# Control_Interface_Board.net
KiCad netlist of a schematic drawn in Altium Designer
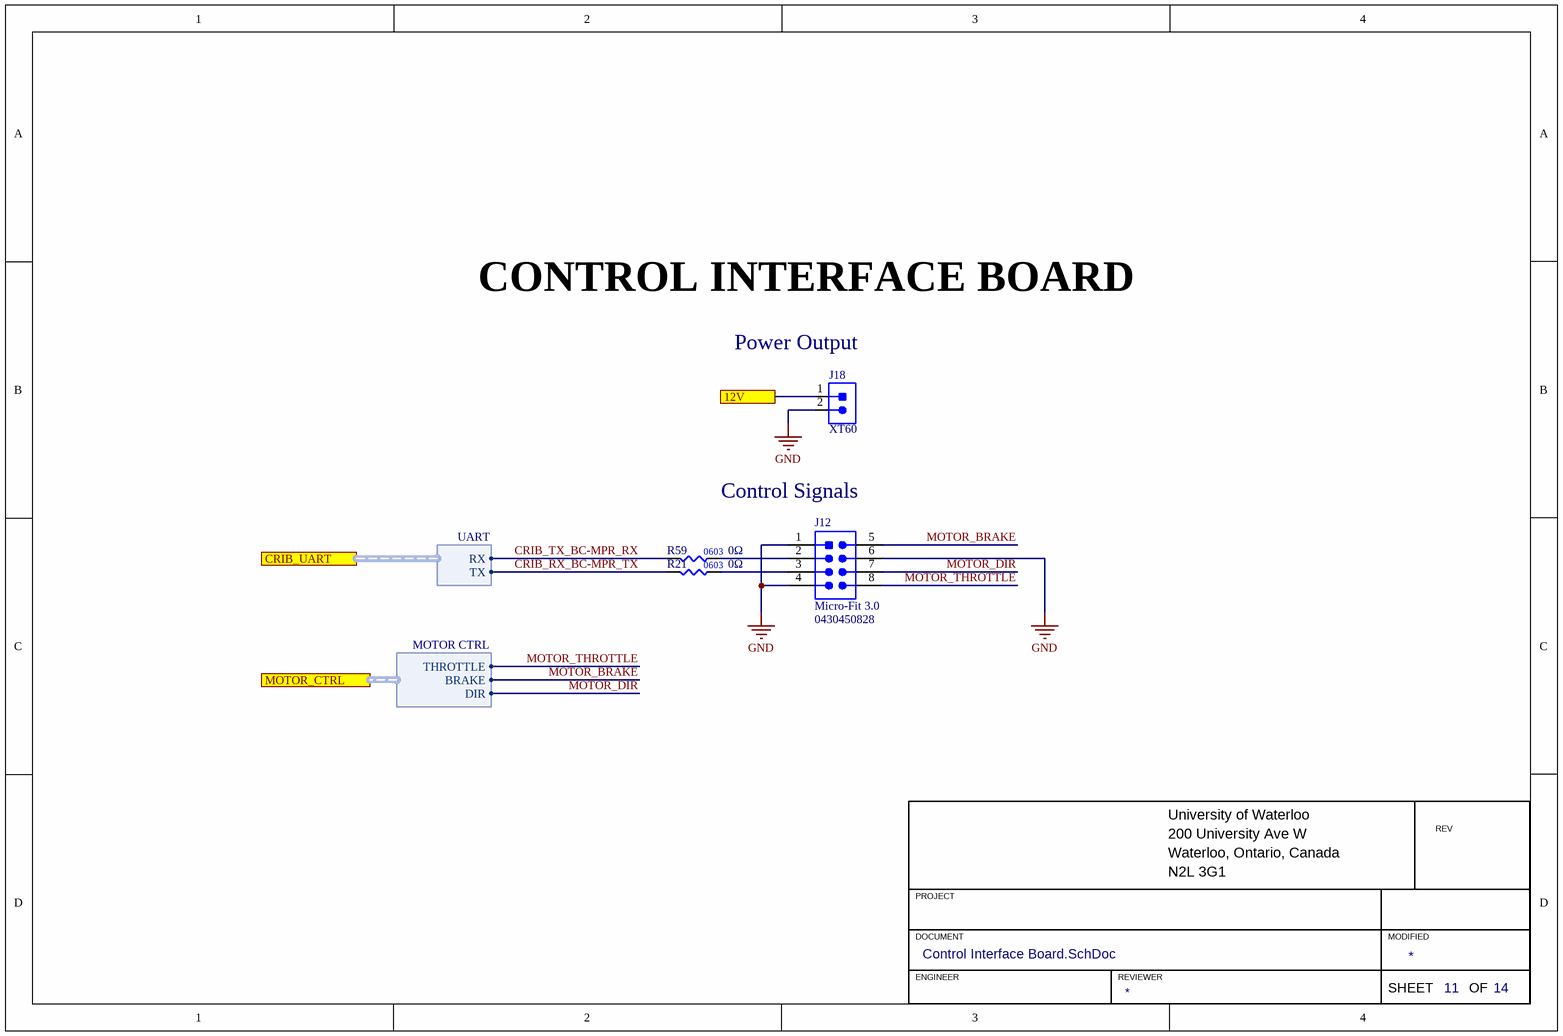
[diagram p0: Control Interface Board.SchDoc]

(export (version "E")
  (design (tool "Eeschema 10.0.6"))
  (components
    (comp (ref "J12")
      (value "0430450828")
      (footprint "MOLEX-0430450828")
      (description "CONN HEADER VERT 8POS 3MM")
      (fields
        (field (name "FAMILY") "Micro-Fit 3.0")
        (field (name "MANUFACTURER PART NUMBER 1") "0430450828")
      )
      (libsource (lib "Personal_Schematic_Library_2022") (part "CON_MOLEX-HDR_4x2_TH"))
    )
    (comp (ref "J18")
      (value "CON_2POS_XT60")
      (footprint "XT60")
      (description "XT60 CONNECTORS MALE/FEMALE PAIR")
      (fields (field (name "PACKAGE/FOOTPRINT") "XT60"))
      (libsource (lib "Personal_Schematic_Library_2022") (part "CON_2POS_XT60"))
    )
    (comp (ref "R21")
      (value "0Ω")
      (footprint "RES0603")
      (description "RES 0 OHM JUMPER 1/10W 0603")
      (fields (field (name "Comment") "RES_0Ω_0603"))
      (libsource (lib "Personal_Schematic_Library_2022") (part "RES_0Ω_0603"))
    )
    (comp (ref "R59")
      (value "0Ω")
      (footprint "RES0603")
      (description "RES 0 OHM JUMPER 1/10W 0603")
      (fields (field (name "Comment") "RES_0Ω_0603"))
      (libsource (lib "Personal_Schematic_Library_2022") (part "RES_0Ω_0603"))
    )
  )
  (nets
    (net (code "4") (name "/12V") (class "Default")
      (node (ref "J18") (pin "1") (pinfunction "1_1") (pintype "passive"))
    )
    (net (code "5") (name "/CRIB_RX_BC-MPR_TX") (class "Default")
      (node (ref "R21") (pin "1") (pinfunction "1_1") (pintype "passive"))
    )
    (net (code "6") (name "/CRIB_TX_BC-MPR_RX") (class "Default")
      (node (ref "R59") (pin "1") (pinfunction "1_1") (pintype "passive"))
    )
    (net (code "7") (name "/MOTOR_BRAKE") (class "Default")
      (node (ref "J12") (pin "5") (pinfunction "5_5") (pintype "passive"))
    )
    (net (code "8") (name "/MOTOR_DIR") (class "Default")
      (node (ref "J12") (pin "7") (pinfunction "7_7") (pintype "passive"))
    )
    (net (code "9") (name "/MOTOR_THROTTLE") (class "Default")
      (node (ref "J12") (pin "8") (pinfunction "8_8") (pintype "passive"))
    )
    (net (code "12") (name "GND") (class "Default")
      (node (ref "J12") (pin "1") (pinfunction "1_1") (pintype "passive"))
      (node (ref "J12") (pin "4") (pinfunction "4_4") (pintype "passive"))
      (node (ref "J12") (pin "6") (pinfunction "6_6") (pintype "passive"))
      (node (ref "J18") (pin "2") (pinfunction "2_2") (pintype "passive"))
    )
    (net (code "13") (name "Net-(J12-Pad2)") (class "Default")
      (node (ref "J12") (pin "2") (pinfunction "2_2") (pintype "passive"))
      (node (ref "R59") (pin "2") (pinfunction "2_2") (pintype "passive"))
    )
    (net (code "14") (name "Net-(J12-Pad3)") (class "Default")
      (node (ref "J12") (pin "3") (pinfunction "3_3") (pintype "passive"))
      (node (ref "R21") (pin "2") (pinfunction "2_2") (pintype "passive"))
    )
  )
)
